# ESP32_and_power.net
KiCad netlist of a schematic drawn in EAGLE
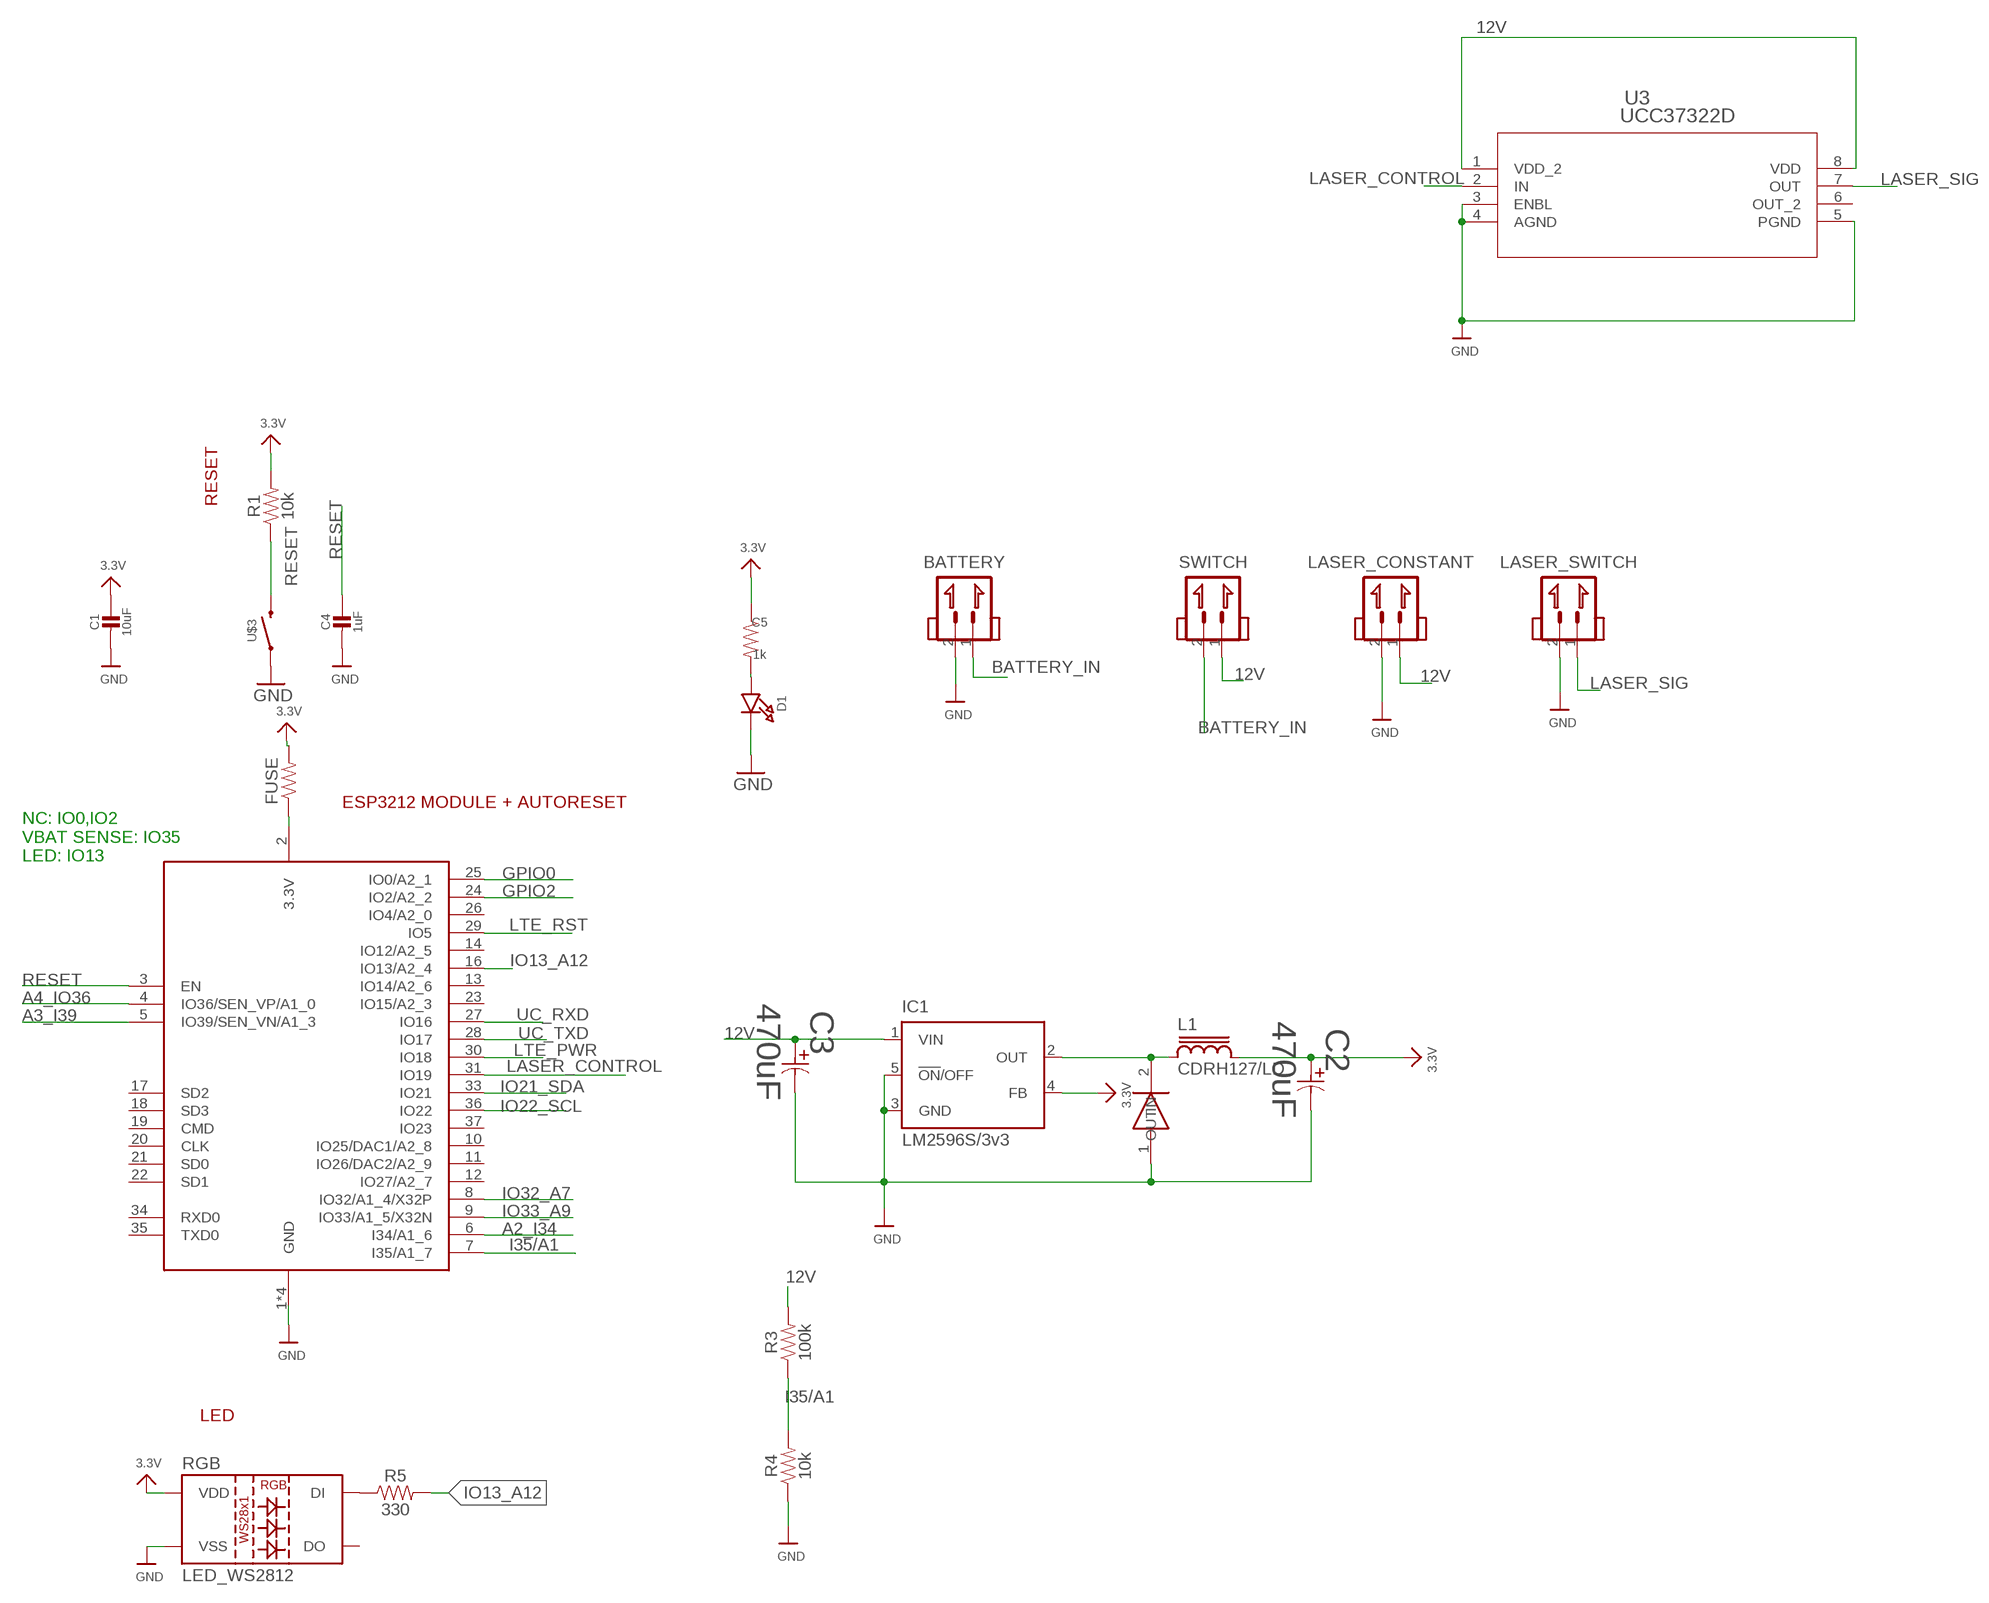
[diagram p0: schematic, sheet 1, part 1 of 2]
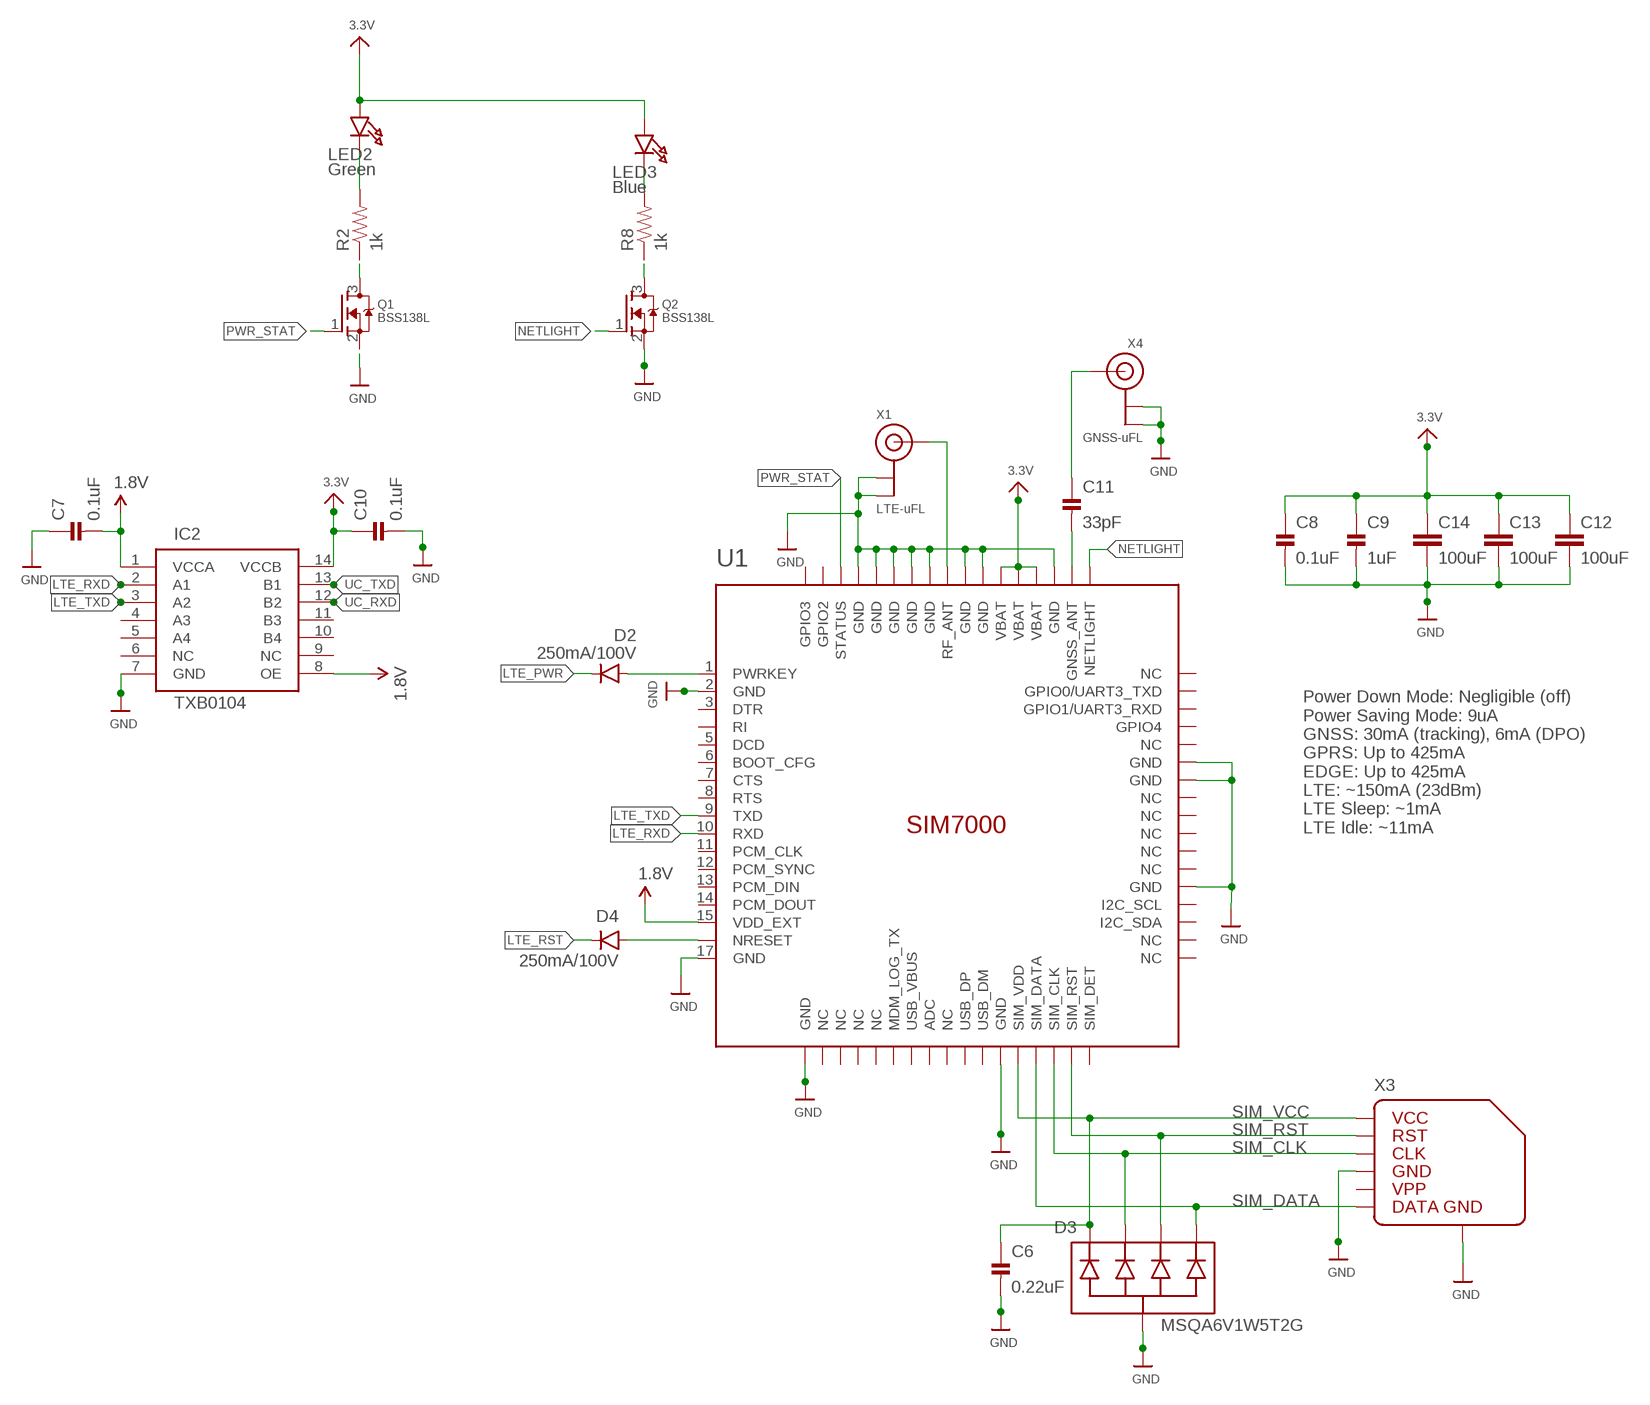
[diagram p1: schematic, sheet 1, part 2 of 2]

(export (version "E")
  (design (tool "Eeschema 10.0.6"))
  (components
    (comp (ref "BATTERY")
      (value "JST_XH_2.54_2P")
      (footprint "eagle-import:JST_XH_2.54_2P")
      (libsource (lib "eagle-import") (part "JST_XH_2.54_2P"))
    )
    (comp (ref "C1")
      (value "10uF")
      (footprint "eagle-import:CAP_0603")
      (libsource (lib "eagle-import") (part "CAP_CERAMIC_0603"))
    )
    (comp (ref "C2")
      (value "470uF")
      (footprint "eagle-import:PCAP_8X10-ELECT")
      (fields (field (name "MANUFACTURER_PART_NUMBER") "UCD1C471MNL1GS"))
      (libsource (lib "eagle-import") (part "UCD1C471MNL1GS"))
    )
    (comp (ref "C3")
      (value "470uF")
      (footprint "eagle-import:PCAP_8X10-ELECT")
      (fields (field (name "MANUFACTURER_PART_NUMBER") "UCD1C471MNL1GS"))
      (libsource (lib "eagle-import") (part "UCD1C471MNL1GS"))
    )
    (comp (ref "C4")
      (value "1uF")
      (footprint "eagle-import:CAP_0603")
      (libsource (lib "eagle-import") (part "CAP_CERAMIC_0603"))
    )
    (comp (ref "C5")
      (value "1k")
      (footprint "eagle-import:0603")
      (libsource (lib "eagle-import") (part "RESISTOR0603"))
    )
    (comp (ref "C6")
      (value "0.22uF")
      (footprint "eagle-import:CAP_0603")
      (libsource (lib "eagle-import") (part "CAP_CERAMIC_0603"))
    )
    (comp (ref "C7")
      (value "0.1uF")
      (footprint "eagle-import:CAP_0603")
      (libsource (lib "eagle-import") (part "CAP_CERAMIC_0603"))
    )
    (comp (ref "C8")
      (value "0.1uF")
      (footprint "eagle-import:CAP_0603")
      (libsource (lib "eagle-import") (part "CAP_CERAMIC_0603"))
    )
    (comp (ref "C9")
      (value "1uF")
      (footprint "eagle-import:CAP_0603")
      (libsource (lib "eagle-import") (part "CAP_CERAMIC_0603"))
    )
    (comp (ref "C10")
      (value "0.1uF")
      (footprint "eagle-import:CAP_0603")
      (libsource (lib "eagle-import") (part "CAP_CERAMIC_0603"))
    )
    (comp (ref "C11")
      (value "33pF")
      (footprint "eagle-import:CAP_0603")
      (libsource (lib "eagle-import") (part "CAP_CERAMIC_0603"))
    )
    (comp (ref "C12")
      (value "100uF")
      (footprint "eagle-import:1210")
      (libsource (lib "eagle-import") (part "CAPMARKED-1210"))
    )
    (comp (ref "C13")
      (value "100uF")
      (footprint "eagle-import:1210")
      (libsource (lib "eagle-import") (part "CAPMARKED-1210"))
    )
    (comp (ref "C14")
      (value "100uF")
      (footprint "eagle-import:1210")
      (libsource (lib "eagle-import") (part "CAPMARKED-1210"))
    )
    (comp (ref "D1")
      (value "LED0603")
      (footprint "eagle-import:MICROBUILDER_CHIPLED_0603")
      (libsource (lib "eagle-import") (part "LED0603"))
    )
    (comp (ref "D2")
      (value "250mA/100V")
      (footprint "eagle-import:SOD-323")
      (libsource (lib "eagle-import") (part "DIODESOD323"))
    )
    (comp (ref "D3")
      (value "MSQA6V1W5T2G")
      (footprint "eagle-import:SOT-353")
      (libsource (lib "eagle-import") (part "TVS-DIODE-ARRAY-4X"))
    )
    (comp (ref "D4")
      (value "250mA/100V")
      (footprint "eagle-import:SOD-323")
      (libsource (lib "eagle-import") (part "DIODESOD323"))
    )
    (comp (ref "FUSE")
      (value "RESISTOR1206")
      (footprint "eagle-import:1206")
      (libsource (lib "eagle-import") (part "RESISTOR1206"))
    )
    (comp (ref "IC1")
      (value "LM2596S/3v3")
      (footprint "eagle-import:TO263-5")
      (fields (field (name "MF") "NATIONAL SEMICONDUCTOR") (field (name "MPN") "LM2596S-ADJ/NOPB"))
      (libsource (lib "eagle-import") (part "LM2596S"))
    )
    (comp (ref "IC2")
      (value "TXB0104")
      (footprint "eagle-import:TSSOP-14")
      (libsource (lib "eagle-import") (part "LEVEL_SHIFTER_TXB0104"))
    )
    (comp (ref "L1")
      (value "CDRH127/LD")
      (footprint "eagle-import:CDRH127_LD")
      (libsource (lib "eagle-import") (part "CDRH127/LD"))
    )
    (comp (ref "LASER_CONSTANT")
      (value "JST_XH_2.54_2P")
      (footprint "eagle-import:JST_XH_2.54_2P")
      (libsource (lib "eagle-import") (part "JST_XH_2.54_2P"))
    )
    (comp (ref "LASER_SWITCH")
      (value "JST_XH_2.54_2P")
      (footprint "eagle-import:JST_XH_2.54_2P")
      (libsource (lib "eagle-import") (part "JST_XH_2.54_2P"))
    )
    (comp (ref "LED2")
      (value "Green")
      (footprint "eagle-import:MICROBUILDER_CHIPLED_0603")
      (libsource (lib "eagle-import") (part "LED0603"))
    )
    (comp (ref "LED3")
      (value "Blue")
      (footprint "eagle-import:MICROBUILDER_CHIPLED_0603")
      (libsource (lib "eagle-import") (part "LED0603"))
    )
    (comp (ref "Q1")
      (value "BSS138L")
      (footprint "eagle-import:SOT23-3")
      (libsource (lib "eagle-import") (part "MOSFET-NGENERIC"))
    )
    (comp (ref "Q2")
      (value "BSS138L")
      (footprint "eagle-import:SOT23-3")
      (libsource (lib "eagle-import") (part "MOSFET-NGENERIC"))
    )
    (comp (ref "R1")
      (value "10k")
      (footprint "eagle-import:0603")
      (libsource (lib "eagle-import") (part "RESISTOR0603"))
    )
    (comp (ref "R2")
      (value "1k")
      (footprint "eagle-import:0603")
      (libsource (lib "eagle-import") (part "RESISTOR0603"))
    )
    (comp (ref "R3")
      (value "100k")
      (footprint "eagle-import:0603")
      (libsource (lib "eagle-import") (part "RESISTOR0603"))
    )
    (comp (ref "R4")
      (value "10k")
      (footprint "eagle-import:0603")
      (libsource (lib "eagle-import") (part "RESISTOR0603"))
    )
    (comp (ref "R5")
      (value "330")
      (footprint "eagle-import:0603")
      (libsource (lib "eagle-import") (part "RESISTOR0603"))
    )
    (comp (ref "R8")
      (value "1k")
      (footprint "eagle-import:0603")
      (libsource (lib "eagle-import") (part "RESISTOR0603"))
    )
    (comp (ref "RGB")
      (value "LED_WS2812")
      (footprint "eagle-import:LED-TRICOLOR-5050-IC")
      (libsource (lib "eagle-import") (part "LED_WS2812"))
    )
    (comp (ref "SS34")
      (value "40V3A")
      (footprint "eagle-import:SMA-SS34")
      (libsource (lib "eagle-import") (part "SMA-SS34"))
    )
    (comp (ref "SWITCH")
      (value "JST_XH_2.54_2P")
      (footprint "eagle-import:JST_XH_2.54_2P")
      (libsource (lib "eagle-import") (part "JST_XH_2.54_2P"))
    )
    (comp (ref "U$3")
      (value "PUSHBUTTON")
      (footprint "eagle-import:TACTILE_SWITCH_SMD_6.0X3.5MM")
      (libsource (lib "eagle-import") (part "PUSHBUTTON"))
    )
    (comp (ref "U1")
      (value "SIM7000")
      (footprint "eagle-import:SIM7000")
      (libsource (lib "eagle-import") (part "SIM7000"))
    )
    (comp (ref "U3")
      (value "UCC37322D")
      (footprint "eagle-import:D8")
      (libsource (lib "eagle-import") (part "UCC37322D"))
    )
    (comp (ref "X1")
      (value "LTE-uFL")
      (footprint "eagle-import:U.FL")
      (libsource (lib "eagle-import") (part "ANTENNA_U.FL"))
    )
    (comp (ref "X2")
      (value "ESP32_WROOM32_SKINNY")
      (footprint "eagle-import:WROOM32_SKINNY")
      (libsource (lib "eagle-import") (part "ESP32_WROOM32_SKINNY"))
    )
    (comp (ref "X3")
      (value "MICROSIM_SOCKET")
      (footprint "eagle-import:MICROSIM_SOCKET")
      (libsource (lib "eagle-import") (part "MICROSIM_SOCKET"))
    )
    (comp (ref "X4")
      (value "GNSS-uFL")
      (footprint "eagle-import:U.FL")
      (libsource (lib "eagle-import") (part "ANTENNA_U.FL"))
    )
  )
  (nets
    (net (code "1") (name "/12V") (class "Default")
      (node (ref "C3") (pin "1") (pinfunction "1_1") (pintype "passive"))
      (node (ref "IC1") (pin "1") (pinfunction "VIN_1") (pintype "input"))
      (node (ref "LASER_CONSTANT") (pin "1") (pinfunction "1_1") (pintype "passive"))
      (node (ref "R3") (pin "2") (pinfunction "2_2") (pintype "passive"))
      (node (ref "SWITCH") (pin "1") (pinfunction "1_1") (pintype "passive"))
      (node (ref "U3") (pin "1") (pinfunction "VDD_2_1") (pintype "power_in"))
      (node (ref "U3") (pin "8") (pinfunction "VDD_8") (pintype "power_in"))
    )
    (net (code "2") (name "/A2_I34") (class "Default")
      (node (ref "X2") (pin "6") (pinfunction "I34/A1_6_6") (pintype "bidirectional"))
    )
    (net (code "3") (name "/A3_I39") (class "Default")
      (node (ref "X2") (pin "5") (pinfunction "IO39/SEN_VN/A1_3_5") (pintype "passive"))
    )
    (net (code "4") (name "/A4_IO36") (class "Default")
      (node (ref "X2") (pin "4") (pinfunction "IO36/SEN_VP/A1_0_4") (pintype "passive"))
    )
    (net (code "5") (name "/BATTERY_IN") (class "Default")
      (node (ref "BATTERY") (pin "1") (pinfunction "1_1") (pintype "passive"))
      (node (ref "SWITCH") (pin "2") (pinfunction "2_2") (pintype "passive"))
    )
    (net (code "6") (name "/GPIO0") (class "Default")
      (node (ref "X2") (pin "25") (pinfunction "IO0/A2_1_25") (pintype "bidirectional"))
    )
    (net (code "7") (name "/GPIO2") (class "Default")
      (node (ref "X2") (pin "24") (pinfunction "IO2/A2_2_24") (pintype "bidirectional"))
    )
    (net (code "8") (name "/I35{slash}A1") (class "Default")
      (node (ref "R3") (pin "1") (pinfunction "1_1") (pintype "passive"))
      (node (ref "R4") (pin "2") (pinfunction "2_2") (pintype "passive"))
      (node (ref "X2") (pin "7") (pinfunction "I35/A1_7_7") (pintype "bidirectional"))
    )
    (net (code "9") (name "/IO21_SDA") (class "Default")
      (node (ref "X2") (pin "33") (pinfunction "IO21_33") (pintype "bidirectional"))
    )
    (net (code "10") (name "/IO22_SCL") (class "Default")
      (node (ref "X2") (pin "36") (pinfunction "IO22_36") (pintype "bidirectional"))
    )
    (net (code "11") (name "/IO32_A7") (class "Default")
      (node (ref "X2") (pin "8") (pinfunction "IO32/A1_4/X32P_8") (pintype "bidirectional"))
    )
    (net (code "12") (name "/IO33_A9") (class "Default")
      (node (ref "X2") (pin "9") (pinfunction "IO33/A1_5/X32N_9") (pintype "bidirectional"))
    )
    (net (code "13") (name "/LASER_CONTROL") (class "Default")
      (node (ref "U3") (pin "2") (pinfunction "IN_2") (pintype "input"))
      (node (ref "X2") (pin "31") (pinfunction "IO19_31") (pintype "bidirectional"))
    )
    (net (code "14") (name "/LASER_SIG") (class "Default")
      (node (ref "LASER_SWITCH") (pin "1") (pinfunction "1_1") (pintype "passive"))
      (node (ref "U3") (pin "7") (pinfunction "OUT_7") (pintype "output"))
    )
    (net (code "15") (name "/RESET") (class "Default")
      (node (ref "C4") (pin "1") (pinfunction "1_1") (pintype "passive"))
      (node (ref "R1") (pin "1") (pinfunction "1_1") (pintype "passive"))
      (node (ref "U$3") (pin "2") (pinfunction "2_2") (pintype "passive"))
      (node (ref "X2") (pin "3") (pinfunction "EN_3") (pintype "input"))
    )
    (net (code "16") (name "/SIM_CLK") (class "Default")
      (node (ref "D3") (pin "3") (pinfunction "2_3") (pintype "bidirectional"))
      (node (ref "U1") (pin "32") (pinfunction "SIM_CLK_32") (pintype "bidirectional"))
      (node (ref "X3") (pin "C3") (pinfunction "C3_C3") (pintype "passive"))
    )
    (net (code "17") (name "/SIM_DATA") (class "Default")
      (node (ref "D3") (pin "5") (pinfunction "4_5") (pintype "bidirectional"))
      (node (ref "U1") (pin "31") (pinfunction "SIM_DATA_31") (pintype "bidirectional"))
      (node (ref "X3") (pin "C7") (pinfunction "C7_C7") (pintype "passive"))
    )
    (net (code "18") (name "/SIM_RST") (class "Default")
      (node (ref "D3") (pin "4") (pinfunction "3_4") (pintype "bidirectional"))
      (node (ref "U1") (pin "33") (pinfunction "SIM_RST_33") (pintype "bidirectional"))
      (node (ref "X3") (pin "C2") (pinfunction "C2_C2") (pintype "passive"))
    )
    (net (code "19") (name "/SIM_VCC") (class "Default")
      (node (ref "C6") (pin "1") (pinfunction "1_1") (pintype "passive"))
      (node (ref "D3") (pin "1") (pinfunction "1_1") (pintype "bidirectional"))
      (node (ref "U1") (pin "30") (pinfunction "SIM_VDD_30") (pintype "bidirectional"))
      (node (ref "X3") (pin "C1") (pinfunction "C1_C1") (pintype "power_in"))
    )
    (net (code "20") (name "1.8V") (class "Default")
      (node (ref "C7") (pin "2") (pinfunction "2_2") (pintype "passive"))
      (node (ref "IC2") (pin "1") (pinfunction "VCCA_1") (pintype "power_in"))
      (node (ref "IC2") (pin "8") (pinfunction "OE_8") (pintype "bidirectional"))
      (node (ref "U1") (pin "15") (pinfunction "VDD_EXT_15") (pintype "bidirectional"))
    )
    (net (code "21") (name "3.3V") (class "Default")
      (node (ref "C1") (pin "1") (pinfunction "1_1") (pintype "passive"))
      (node (ref "C10") (pin "1") (pinfunction "1_1") (pintype "passive"))
      (node (ref "C12") (pin "1") (pinfunction "1_1") (pintype "passive"))
      (node (ref "C13") (pin "1") (pinfunction "1_1") (pintype "passive"))
      (node (ref "C14") (pin "1") (pinfunction "1_1") (pintype "passive"))
      (node (ref "C2") (pin "1") (pinfunction "1_1") (pintype "passive"))
      (node (ref "C5") (pin "1") (pinfunction "1_1") (pintype "passive"))
      (node (ref "C8") (pin "1") (pinfunction "1_1") (pintype "passive"))
      (node (ref "C9") (pin "1") (pinfunction "1_1") (pintype "passive"))
      (node (ref "FUSE") (pin "2") (pinfunction "2_2") (pintype "passive"))
      (node (ref "IC1") (pin "4") (pinfunction "FB_4") (pintype "input"))
      (node (ref "IC2") (pin "14") (pinfunction "VCCB_14") (pintype "power_in"))
      (node (ref "L1") (pin "2") (pinfunction "2_2") (pintype "passive"))
      (node (ref "LED2") (pin "A") (pinfunction "A_A") (pintype "passive"))
      (node (ref "LED3") (pin "A") (pinfunction "A_A") (pintype "passive"))
      (node (ref "R1") (pin "2") (pinfunction "2_2") (pintype "passive"))
      (node (ref "RGB") (pin "VDD") (pinfunction "VDD_VDD") (pintype "bidirectional"))
      (node (ref "U1") (pin "55") (pinfunction "VBAT_55") (pintype "bidirectional"))
      (node (ref "U1") (pin "56") (pinfunction "VBAT_56") (pintype "bidirectional"))
      (node (ref "U1") (pin "57") (pinfunction "VBAT_57") (pintype "bidirectional"))
    )
    (net (code "22") (name "GND") (class "Default")
      (node (ref "BATTERY") (pin "2") (pinfunction "2_2") (pintype "passive"))
      (node (ref "C1") (pin "2") (pinfunction "2_2") (pintype "passive"))
      (node (ref "C10") (pin "2") (pinfunction "2_2") (pintype "passive"))
      (node (ref "C12") (pin "2") (pinfunction "2_2") (pintype "passive"))
      (node (ref "C13") (pin "2") (pinfunction "2_2") (pintype "passive"))
      (node (ref "C14") (pin "2") (pinfunction "2_2") (pintype "passive"))
      (node (ref "C2") (pin "2") (pinfunction "2_2") (pintype "passive"))
      (node (ref "C3") (pin "2") (pinfunction "2_2") (pintype "passive"))
      (node (ref "C4") (pin "2") (pinfunction "2_2") (pintype "passive"))
      (node (ref "C6") (pin "2") (pinfunction "2_2") (pintype "passive"))
      (node (ref "C7") (pin "1") (pinfunction "1_1") (pintype "passive"))
      (node (ref "C8") (pin "2") (pinfunction "2_2") (pintype "passive"))
      (node (ref "C9") (pin "2") (pinfunction "2_2") (pintype "passive"))
      (node (ref "D1") (pin "C") (pinfunction "C_C") (pintype "passive"))
      (node (ref "D3") (pin "2") (pinfunction "COM_2") (pintype "bidirectional"))
      (node (ref "IC1") (pin "3") (pinfunction "GND_3") (pintype "power_in"))
      (node (ref "IC1") (pin "5") (pinfunction "~{ON}/OFF_5") (pintype "input"))
      (node (ref "IC2") (pin "7") (pinfunction "GND_7") (pintype "power_in"))
      (node (ref "LASER_CONSTANT") (pin "2") (pinfunction "2_2") (pintype "passive"))
      (node (ref "LASER_SWITCH") (pin "2") (pinfunction "2_2") (pintype "passive"))
      (node (ref "Q1") (pin "2") (pinfunction "S_2") (pintype "bidirectional"))
      (node (ref "Q2") (pin "2") (pinfunction "S_2") (pintype "bidirectional"))
      (node (ref "R4") (pin "1") (pinfunction "1_1") (pintype "passive"))
      (node (ref "RGB") (pin "VSS") (pinfunction "VSS_VSS") (pintype "bidirectional"))
      (node (ref "SS34") (pin "1") (pinfunction "IN_1") (pintype "input"))
      (node (ref "U$3") (pin "1") (pinfunction "1_1") (pintype "passive"))
      (node (ref "U1") (pin "17") (pinfunction "GND_17") (pintype "bidirectional"))
      (node (ref "U1") (pin "18") (pinfunction "GND_18") (pintype "bidirectional"))
      (node (ref "U1") (pin "2") (pinfunction "GND_2") (pintype "bidirectional"))
      (node (ref "U1") (pin "29") (pinfunction "GND_29") (pintype "bidirectional"))
      (node (ref "U1") (pin "39") (pinfunction "GND_39") (pintype "bidirectional"))
      (node (ref "U1") (pin "45") (pinfunction "GND_45") (pintype "bidirectional"))
      (node (ref "U1") (pin "46") (pinfunction "GND_46") (pintype "bidirectional"))
      (node (ref "U1") (pin "54") (pinfunction "GND_54") (pintype "bidirectional"))
      (node (ref "U1") (pin "58") (pinfunction "GND_58") (pintype "bidirectional"))
      (node (ref "U1") (pin "59") (pinfunction "GND_59") (pintype "bidirectional"))
      (node (ref "U1") (pin "61") (pinfunction "GND_61") (pintype "bidirectional"))
      (node (ref "U1") (pin "62") (pinfunction "GND_62") (pintype "bidirectional"))
      (node (ref "U1") (pin "63") (pinfunction "GND_63") (pintype "bidirectional"))
      (node (ref "U1") (pin "64") (pinfunction "GND_64") (pintype "bidirectional"))
      (node (ref "U1") (pin "65") (pinfunction "GND_65") (pintype "bidirectional"))
      (node (ref "U3") (pin "3") (pinfunction "ENBL_3") (pintype "passive"))
      (node (ref "U3") (pin "4") (pinfunction "AGND_4") (pintype "power_in"))
      (node (ref "U3") (pin "5") (pinfunction "PGND_5") (pintype "power_in"))
      (node (ref "X1") (pin "1") (pinfunction "GND_1") (pintype "passive"))
      (node (ref "X1") (pin "2") (pinfunction "GND_2") (pintype "passive"))
      (node (ref "X2") (pin "1") (pinfunction "GND_1") (pintype "passive"))
      (node (ref "X2") (pin "15") (pinfunction "GND_15") (pintype "passive"))
      (node (ref "X2") (pin "38") (pinfunction "GND_38") (pintype "passive"))
      (node (ref "X2") (pin "P$1") (pinfunction "GND_P$1") (pintype "passive"))
      (node (ref "X3") (pin "C5") (pinfunction "C5_C5") (pintype "power_in"))
      (node (ref "X3") (pin "GND@1") (pinfunction "GND_GND@1") (pintype "power_in"))
      (node (ref "X3") (pin "GND@2") (pinfunction "GND_GND@2") (pintype "power_in"))
      (node (ref "X3") (pin "GND@3") (pinfunction "GND_GND@3") (pintype "power_in"))
      (node (ref "X3") (pin "GND@4") (pinfunction "GND_GND@4") (pintype "power_in"))
      (node (ref "X4") (pin "1") (pinfunction "GND_1") (pintype "passive"))
      (node (ref "X4") (pin "2") (pinfunction "GND_2") (pintype "passive"))
    )
    (net (code "23") (name "IO13_A12") (class "Default")
      (node (ref "R5") (pin "2") (pinfunction "2_2") (pintype "passive"))
      (node (ref "X2") (pin "16") (pinfunction "IO13/A2_4_16") (pintype "bidirectional"))
    )
    (net (code "24") (name "LTE_PWR") (class "Default")
      (node (ref "D2") (pin "C") (pinfunction "C_C") (pintype "passive"))
      (node (ref "X2") (pin "30") (pinfunction "IO18_30") (pintype "bidirectional"))
    )
    (net (code "25") (name "LTE_RST") (class "Default")
      (node (ref "D4") (pin "C") (pinfunction "C_C") (pintype "passive"))
      (node (ref "X2") (pin "29") (pinfunction "IO5_29") (pintype "bidirectional"))
    )
    (net (code "26") (name "LTE_RXD") (class "Default")
      (node (ref "IC2") (pin "2") (pinfunction "A1_2") (pintype "bidirectional"))
      (node (ref "U1") (pin "10") (pinfunction "RXD_10") (pintype "bidirectional"))
    )
    (net (code "27") (name "LTE_TXD") (class "Default")
      (node (ref "IC2") (pin "3") (pinfunction "A2_3") (pintype "bidirectional"))
      (node (ref "U1") (pin "9") (pinfunction "TXD_9") (pintype "bidirectional"))
    )
    (net (code "28") (name "NETLIGHT") (class "Default")
      (node (ref "Q2") (pin "1") (pinfunction "G_1") (pintype "bidirectional"))
      (node (ref "U1") (pin "52") (pinfunction "NETLIGHT_52") (pintype "bidirectional"))
    )
    (net (code "29") (name "Net-(C5-Pad2)") (class "Default")
      (node (ref "C5") (pin "2") (pinfunction "2_2") (pintype "passive"))
      (node (ref "D1") (pin "A") (pinfunction "A_A") (pintype "passive"))
    )
    (net (code "30") (name "Net-(IC1-OUT)") (class "Default")
      (node (ref "IC1") (pin "2") (pinfunction "OUT_2") (pintype "output"))
      (node (ref "L1") (pin "1") (pinfunction "1_1") (pintype "passive"))
      (node (ref "SS34") (pin "2") (pinfunction "OUT_2") (pintype "bidirectional"))
    )
    (net (code "31") (name "Net-(LED2-PadC)") (class "Default")
      (node (ref "LED2") (pin "C") (pinfunction "C_C") (pintype "passive"))
      (node (ref "R2") (pin "2") (pinfunction "2_2") (pintype "passive"))
    )
    (net (code "32") (name "Net-(LED3-PadC)") (class "Default")
      (node (ref "LED3") (pin "C") (pinfunction "C_C") (pintype "passive"))
      (node (ref "R8") (pin "2") (pinfunction "2_2") (pintype "passive"))
    )
    (net (code "33") (name "Net-(Q1-D)") (class "Default")
      (node (ref "Q1") (pin "3") (pinfunction "D_3") (pintype "bidirectional"))
      (node (ref "R2") (pin "1") (pinfunction "1_1") (pintype "passive"))
    )
    (net (code "34") (name "Net-(Q2-D)") (class "Default")
      (node (ref "Q2") (pin "3") (pinfunction "D_3") (pintype "bidirectional"))
      (node (ref "R8") (pin "1") (pinfunction "1_1") (pintype "passive"))
    )
    (net (code "35") (name "Net-(RGB-DI)") (class "Default")
      (node (ref "R5") (pin "1") (pinfunction "1_1") (pintype "passive"))
      (node (ref "RGB") (pin "DIN") (pinfunction "DI_DIN") (pintype "bidirectional"))
    )
    (net (code "36") (name "Net-(U1-GNSS_ANT)") (class "Default")
      (node (ref "C11") (pin "2") (pinfunction "2_2") (pintype "passive"))
      (node (ref "U1") (pin "53") (pinfunction "GNSS_ANT_53") (pintype "bidirectional"))
    )
    (net (code "37") (name "Net-(U1-NRESET)") (class "Default")
      (node (ref "D4") (pin "A") (pinfunction "A_A") (pintype "passive"))
      (node (ref "U1") (pin "16") (pinfunction "NRESET_16") (pintype "bidirectional"))
    )
    (net (code "38") (name "Net-(U1-PWRKEY)") (class "Default")
      (node (ref "D2") (pin "A") (pinfunction "A_A") (pintype "passive"))
      (node (ref "U1") (pin "1") (pinfunction "PWRKEY_1") (pintype "bidirectional"))
    )
    (net (code "39") (name "Net-(U1-RF_ANT)") (class "Default")
      (node (ref "U1") (pin "60") (pinfunction "RF_ANT_60") (pintype "bidirectional"))
      (node (ref "X1") (pin "3") (pinfunction "SIGNAL_3") (pintype "passive"))
    )
    (net (code "40") (name "Net-(X2-3.3V)") (class "Default")
      (node (ref "FUSE") (pin "1") (pinfunction "1_1") (pintype "passive"))
      (node (ref "X2") (pin "2") (pinfunction "3.3V_2") (pintype "passive"))
    )
    (net (code "41") (name "Net-(X4-SIGNAL)") (class "Default")
      (node (ref "C11") (pin "1") (pinfunction "1_1") (pintype "passive"))
      (node (ref "X4") (pin "3") (pinfunction "SIGNAL_3") (pintype "passive"))
    )
    (net (code "42") (name "PWR_STAT") (class "Default")
      (node (ref "Q1") (pin "1") (pinfunction "G_1") (pintype "bidirectional"))
      (node (ref "U1") (pin "66") (pinfunction "STATUS_66") (pintype "bidirectional"))
    )
    (net (code "43") (name "UC_RXD") (class "Default")
      (node (ref "IC2") (pin "12") (pinfunction "B2_12") (pintype "bidirectional"))
      (node (ref "X2") (pin "27") (pinfunction "IO16_27") (pintype "bidirectional"))
    )
    (net (code "44") (name "UC_TXD") (class "Default")
      (node (ref "IC2") (pin "13") (pinfunction "B1_13") (pintype "bidirectional"))
      (node (ref "X2") (pin "28") (pinfunction "IO17_28") (pintype "bidirectional"))
    )
    (net (code "45") (name "unconnected-(IC2-A3-Pad4)") (class "Default")
      (node (ref "IC2") (pin "4") (pinfunction "A3_4") (pintype "bidirectional"))
    )
    (net (code "46") (name "unconnected-(IC2-A4-Pad5)") (class "Default")
      (node (ref "IC2") (pin "5") (pinfunction "A4_5") (pintype "bidirectional"))
    )
    (net (code "47") (name "unconnected-(IC2-B3-Pad11)") (class "Default")
      (node (ref "IC2") (pin "11") (pinfunction "B3_11") (pintype "bidirectional"))
    )
    (net (code "48") (name "unconnected-(IC2-B4-Pad10)") (class "Default")
      (node (ref "IC2") (pin "10") (pinfunction "B4_10") (pintype "bidirectional"))
    )
    (net (code "49") (name "unconnected-(IC2-NC-Pad6)") (class "Default")
      (node (ref "IC2") (pin "6") (pinfunction "NC_6") (pintype "bidirectional"))
    )
    (net (code "50") (name "unconnected-(IC2-NC-Pad9)") (class "Default")
      (node (ref "IC2") (pin "9") (pinfunction "NC_9") (pintype "bidirectional"))
    )
    (net (code "51") (name "unconnected-(RGB-DO-PadDOUT)") (class "Default")
      (node (ref "RGB") (pin "DOUT") (pinfunction "DO_DOUT") (pintype "bidirectional"))
    )
    (net (code "52") (name "unconnected-(U1-ADC-Pad25)") (class "Default")
      (node (ref "U1") (pin "25") (pinfunction "ADC_25") (pintype "bidirectional"))
    )
    (net (code "53") (name "unconnected-(U1-BOOT_CFG-Pad6)") (class "Default")
      (node (ref "U1") (pin "6") (pinfunction "BOOT_CFG_6") (pintype "bidirectional"))
    )
    (net (code "54") (name "unconnected-(U1-CTS-Pad7)") (class "Default")
      (node (ref "U1") (pin "7") (pinfunction "CTS_7") (pintype "bidirectional"))
    )
    (net (code "55") (name "unconnected-(U1-DCD-Pad5)") (class "Default")
      (node (ref "U1") (pin "5") (pinfunction "DCD_5") (pintype "bidirectional"))
    )
    (net (code "56") (name "unconnected-(U1-DTR-Pad3)") (class "Default")
      (node (ref "U1") (pin "3") (pinfunction "DTR_3") (pintype "bidirectional"))
    )
    (net (code "57") (name "unconnected-(U1-GPIO0{slash}UART3_TXD-Pad50)") (class "Default")
      (node (ref "U1") (pin "50") (pinfunction "GPIO0/UART3_TXD_50") (pintype "bidirectional"))
    )
    (net (code "58") (name "unconnected-(U1-GPIO1{slash}UART3_RXD-Pad49)") (class "Default")
      (node (ref "U1") (pin "49") (pinfunction "GPIO1/UART3_RXD_49") (pintype "bidirectional"))
    )
    (net (code "59") (name "unconnected-(U1-GPIO2-Pad67)") (class "Default")
      (node (ref "U1") (pin "67") (pinfunction "GPIO2_67") (pintype "bidirectional"))
    )
    (net (code "60") (name "unconnected-(U1-GPIO3-Pad68)") (class "Default")
      (node (ref "U1") (pin "68") (pinfunction "GPIO3_68") (pintype "bidirectional"))
    )
    (net (code "61") (name "unconnected-(U1-GPIO4-Pad48)") (class "Default")
      (node (ref "U1") (pin "48") (pinfunction "GPIO4_48") (pintype "bidirectional"))
    )
    (net (code "62") (name "unconnected-(U1-I2C_SCL-Pad38)") (class "Default")
      (node (ref "U1") (pin "38") (pinfunction "I2C_SCL_38") (pintype "bidirectional"))
    )
    (net (code "63") (name "unconnected-(U1-I2C_SDA-Pad37)") (class "Default")
      (node (ref "U1") (pin "37") (pinfunction "I2C_SDA_37") (pintype "bidirectional"))
    )
    (net (code "64") (name "unconnected-(U1-MDM_LOG_TX-Pad23)") (class "Default")
      (node (ref "U1") (pin "23") (pinfunction "MDM_LOG_TX_23") (pintype "bidirectional"))
    )
    (net (code "65") (name "unconnected-(U1-NC-Pad19)") (class "Default")
      (node (ref "U1") (pin "19") (pinfunction "NC_19") (pintype "bidirectional"))
    )
    (net (code "66") (name "unconnected-(U1-NC-Pad20)") (class "Default")
      (node (ref "U1") (pin "20") (pinfunction "NC_20") (pintype "bidirectional"))
    )
    (net (code "67") (name "unconnected-(U1-NC-Pad21)") (class "Default")
      (node (ref "U1") (pin "21") (pinfunction "NC_21") (pintype "bidirectional"))
    )
    (net (code "68") (name "unconnected-(U1-NC-Pad22)") (class "Default")
      (node (ref "U1") (pin "22") (pinfunction "NC_22") (pintype "bidirectional"))
    )
    (net (code "69") (name "unconnected-(U1-NC-Pad26)") (class "Default")
      (node (ref "U1") (pin "26") (pinfunction "NC_26") (pintype "bidirectional"))
    )
    (net (code "70") (name "unconnected-(U1-NC-Pad35)") (class "Default")
      (node (ref "U1") (pin "35") (pinfunction "NC_35") (pintype "bidirectional"))
    )
    (net (code "71") (name "unconnected-(U1-NC-Pad36)") (class "Default")
      (node (ref "U1") (pin "36") (pinfunction "NC_36") (pintype "bidirectional"))
    )
    (net (code "72") (name "unconnected-(U1-NC-Pad40)") (class "Default")
      (node (ref "U1") (pin "40") (pinfunction "NC_40") (pintype "bidirectional"))
    )
    (net (code "73") (name "unconnected-(U1-NC-Pad41)") (class "Default")
      (node (ref "U1") (pin "41") (pinfunction "NC_41") (pintype "bidirectional"))
    )
    (net (code "74") (name "unconnected-(U1-NC-Pad42)") (class "Default")
      (node (ref "U1") (pin "42") (pinfunction "NC_42") (pintype "bidirectional"))
    )
    (net (code "75") (name "unconnected-(U1-NC-Pad43)") (class "Default")
      (node (ref "U1") (pin "43") (pinfunction "NC_43") (pintype "bidirectional"))
    )
    (net (code "76") (name "unconnected-(U1-NC-Pad44)") (class "Default")
      (node (ref "U1") (pin "44") (pinfunction "NC_44") (pintype "bidirectional"))
    )
    (net (code "77") (name "unconnected-(U1-NC-Pad47)") (class "Default")
      (node (ref "U1") (pin "47") (pinfunction "NC_47") (pintype "bidirectional"))
    )
    (net (code "78") (name "unconnected-(U1-NC-Pad51)") (class "Default")
      (node (ref "U1") (pin "51") (pinfunction "NC_51") (pintype "bidirectional"))
    )
    (net (code "79") (name "unconnected-(U1-PCM_CLK-Pad11)") (class "Default")
      (node (ref "U1") (pin "11") (pinfunction "PCM_CLK_11") (pintype "bidirectional"))
    )
    (net (code "80") (name "unconnected-(U1-PCM_DIN-Pad13)") (class "Default")
      (node (ref "U1") (pin "13") (pinfunction "PCM_DIN_13") (pintype "bidirectional"))
    )
    (net (code "81") (name "unconnected-(U1-PCM_DOUT-Pad14)") (class "Default")
      (node (ref "U1") (pin "14") (pinfunction "PCM_DOUT_14") (pintype "bidirectional"))
    )
    (net (code "82") (name "unconnected-(U1-PCM_SYNC-Pad12)") (class "Default")
      (node (ref "U1") (pin "12") (pinfunction "PCM_SYNC_12") (pintype "bidirectional"))
    )
    (net (code "83") (name "unconnected-(U1-RI-Pad4)") (class "Default")
      (node (ref "U1") (pin "4") (pinfunction "RI_4") (pintype "bidirectional"))
    )
    (net (code "84") (name "unconnected-(U1-RTS-Pad8)") (class "Default")
      (node (ref "U1") (pin "8") (pinfunction "RTS_8") (pintype "bidirectional"))
    )
    (net (code "85") (name "unconnected-(U1-SIM_DET-Pad34)") (class "Default")
      (node (ref "U1") (pin "34") (pinfunction "SIM_DET_34") (pintype "bidirectional"))
    )
    (net (code "86") (name "unconnected-(U1-USB_DM-Pad28)") (class "Default")
      (node (ref "U1") (pin "28") (pinfunction "USB_DM_28") (pintype "bidirectional"))
    )
    (net (code "87") (name "unconnected-(U1-USB_DP-Pad27)") (class "Default")
      (node (ref "U1") (pin "27") (pinfunction "USB_DP_27") (pintype "bidirectional"))
    )
    (net (code "88") (name "unconnected-(U1-USB_VBUS-Pad24)") (class "Default")
      (node (ref "U1") (pin "24") (pinfunction "USB_VBUS_24") (pintype "bidirectional"))
    )
    (net (code "89") (name "unconnected-(U3-OUT_2-Pad6)") (class "Default")
      (node (ref "U3") (pin "6") (pinfunction "OUT_2_6") (pintype "output"))
    )
    (net (code "90") (name "unconnected-(X2-CLK-Pad20)") (class "Default")
      (node (ref "X2") (pin "20") (pinfunction "CLK_20") (pintype "bidirectional"))
    )
    (net (code "91") (name "unconnected-(X2-CMD-Pad19)") (class "Default")
      (node (ref "X2") (pin "19") (pinfunction "CMD_19") (pintype "bidirectional"))
    )
    (net (code "92") (name "unconnected-(X2-IO4{slash}A2_0-Pad26)") (class "Default")
      (node (ref "X2") (pin "26") (pinfunction "IO4/A2_0_26") (pintype "bidirectional"))
    )
    (net (code "93") (name "unconnected-(X2-IO12{slash}A2_5-Pad14)") (class "Default")
      (node (ref "X2") (pin "14") (pinfunction "IO12/A2_5_14") (pintype "bidirectional"))
    )
    (net (code "94") (name "unconnected-(X2-IO14{slash}A2_6-Pad13)") (class "Default")
      (node (ref "X2") (pin "13") (pinfunction "IO14/A2_6_13") (pintype "bidirectional"))
    )
    (net (code "95") (name "unconnected-(X2-IO15{slash}A2_3-Pad23)") (class "Default")
      (node (ref "X2") (pin "23") (pinfunction "IO15/A2_3_23") (pintype "bidirectional"))
    )
    (net (code "96") (name "unconnected-(X2-IO23-Pad37)") (class "Default")
      (node (ref "X2") (pin "37") (pinfunction "IO23_37") (pintype "bidirectional"))
    )
    (net (code "97") (name "unconnected-(X2-IO25{slash}DAC1{slash}A2_8-Pad10)") (class "Default")
      (node (ref "X2") (pin "10") (pinfunction "IO25/DAC1/A2_8_10") (pintype "bidirectional"))
    )
    (net (code "98") (name "unconnected-(X2-IO26{slash}DAC2{slash}A2_9-Pad11)") (class "Default")
      (node (ref "X2") (pin "11") (pinfunction "IO26/DAC2/A2_9_11") (pintype "bidirectional"))
    )
    (net (code "99") (name "unconnected-(X2-IO27{slash}A2_7-Pad12)") (class "Default")
      (node (ref "X2") (pin "12") (pinfunction "IO27/A2_7_12") (pintype "bidirectional"))
    )
    (net (code "100") (name "unconnected-(X2-RXD0-Pad34)") (class "Default")
      (node (ref "X2") (pin "34") (pinfunction "RXD0_34") (pintype "input"))
    )
    (net (code "101") (name "unconnected-(X2-SD0-Pad21)") (class "Default")
      (node (ref "X2") (pin "21") (pinfunction "SD0_21") (pintype "bidirectional"))
    )
    (net (code "102") (name "unconnected-(X2-SD1-Pad22)") (class "Default")
      (node (ref "X2") (pin "22") (pinfunction "SD1_22") (pintype "bidirectional"))
    )
    (net (code "103") (name "unconnected-(X2-SD2-Pad17)") (class "Default")
      (node (ref "X2") (pin "17") (pinfunction "SD2_17") (pintype "bidirectional"))
    )
    (net (code "104") (name "unconnected-(X2-SD3-Pad18)") (class "Default")
      (node (ref "X2") (pin "18") (pinfunction "SD3_18") (pintype "bidirectional"))
    )
    (net (code "105") (name "unconnected-(X2-TXD0-Pad35)") (class "Default")
      (node (ref "X2") (pin "35") (pinfunction "TXD0_35") (pintype "output"))
    )
    (net (code "106") (name "unconnected-(X3-PadC6)") (class "Default")
      (node (ref "X3") (pin "C6") (pinfunction "C6_C6") (pintype "passive"))
    )
  )
)
